# VerticalPCBConnection.net
KiCad netlist of a schematic drawn in Altium Designer
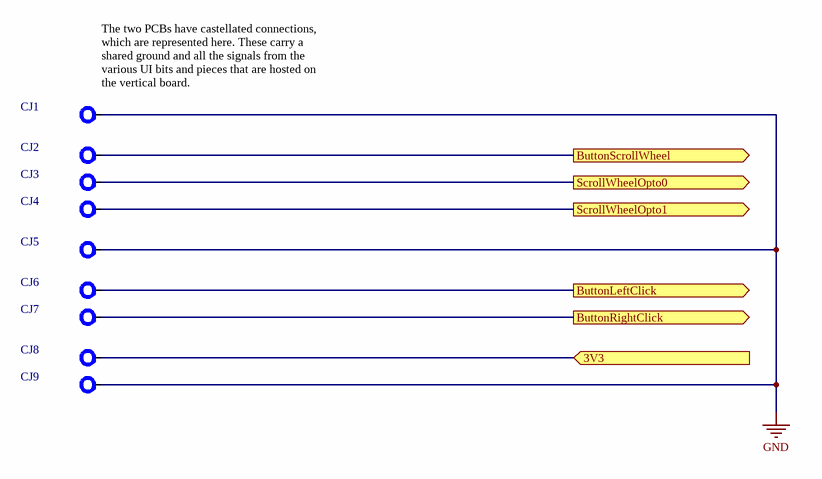
[diagram p0: VerticalPCBConnection.SchDoc]

(export (version "E")
  (design (tool "Eeschema 10.0.6"))
  (components
    (comp (ref "CJ1")
      (value "PCBJointCastellationJoint")
      (footprint "PCBJoint")
      (description "Pad for soldering a castellated PCB edge. Easy way to join two PCBs together.")
      (libsource (lib "PCBFeatures") (part "PCBJoint"))
    )
    (comp (ref "CJ2")
      (value "PCBJointCastellationJoint")
      (footprint "PCBJoint")
      (description "Pad for soldering a castellated PCB edge. Easy way to join two PCBs together.")
      (libsource (lib "PCBFeatures") (part "PCBJoint"))
    )
    (comp (ref "CJ3")
      (value "PCBJointCastellationJoint")
      (footprint "PCBJoint")
      (description "Pad for soldering a castellated PCB edge. Easy way to join two PCBs together.")
      (libsource (lib "PCBFeatures") (part "PCBJoint"))
    )
    (comp (ref "CJ4")
      (value "PCBJointCastellationJoint")
      (footprint "PCBJoint")
      (description "Pad for soldering a castellated PCB edge. Easy way to join two PCBs together.")
      (libsource (lib "PCBFeatures") (part "PCBJoint"))
    )
    (comp (ref "CJ5")
      (value "PCBJointCastellationJoint")
      (footprint "PCBJoint")
      (description "Pad for soldering a castellated PCB edge. Easy way to join two PCBs together.")
      (libsource (lib "PCBFeatures") (part "PCBJoint"))
    )
    (comp (ref "CJ6")
      (value "PCBJointCastellationJoint")
      (footprint "PCBJoint")
      (description "Pad for soldering a castellated PCB edge. Easy way to join two PCBs together.")
      (libsource (lib "PCBFeatures") (part "PCBJoint"))
    )
    (comp (ref "CJ7")
      (value "PCBJointCastellationJoint")
      (footprint "PCBJoint")
      (description "Pad for soldering a castellated PCB edge. Easy way to join two PCBs together.")
      (libsource (lib "PCBFeatures") (part "PCBJoint"))
    )
    (comp (ref "CJ8")
      (value "PCBJointCastellationJoint")
      (footprint "PCBJoint")
      (description "Pad for soldering a castellated PCB edge. Easy way to join two PCBs together.")
      (libsource (lib "PCBFeatures") (part "PCBJoint"))
    )
    (comp (ref "CJ9")
      (value "PCBJointCastellationJoint")
      (footprint "PCBJoint")
      (description "Pad for soldering a castellated PCB edge. Easy way to join two PCBs together.")
      (libsource (lib "PCBFeatures") (part "PCBJoint"))
    )
  )
  (nets
    (net (code "1") (name "/3V3") (class "Default")
      (node (ref "CJ8") (pin "1") (pinfunction "1_1") (pintype "passive"))
    )
    (net (code "2") (name "/ButtonLeftClick") (class "Default")
      (node (ref "CJ6") (pin "1") (pinfunction "1_1") (pintype "passive"))
    )
    (net (code "3") (name "/ButtonRightClick") (class "Default")
      (node (ref "CJ7") (pin "1") (pinfunction "1_1") (pintype "passive"))
    )
    (net (code "4") (name "/ButtonScrollWheel") (class "Default")
      (node (ref "CJ2") (pin "1") (pinfunction "1_1") (pintype "passive"))
    )
    (net (code "5") (name "/ScrollWheelOpto0") (class "Default")
      (node (ref "CJ3") (pin "1") (pinfunction "1_1") (pintype "passive"))
    )
    (net (code "6") (name "/ScrollWheelOpto1") (class "Default")
      (node (ref "CJ4") (pin "1") (pinfunction "1_1") (pintype "passive"))
    )
    (net (code "7") (name "GND") (class "Default")
      (node (ref "CJ1") (pin "1") (pinfunction "1_1") (pintype "passive"))
      (node (ref "CJ5") (pin "1") (pinfunction "1_1") (pintype "passive"))
      (node (ref "CJ9") (pin "1") (pinfunction "1_1") (pintype "passive"))
    )
  )
)
